# reTerm-HW-M-IOLINK-SUPPLY.net
KiCad netlist of a schematic drawn in Altium Designer
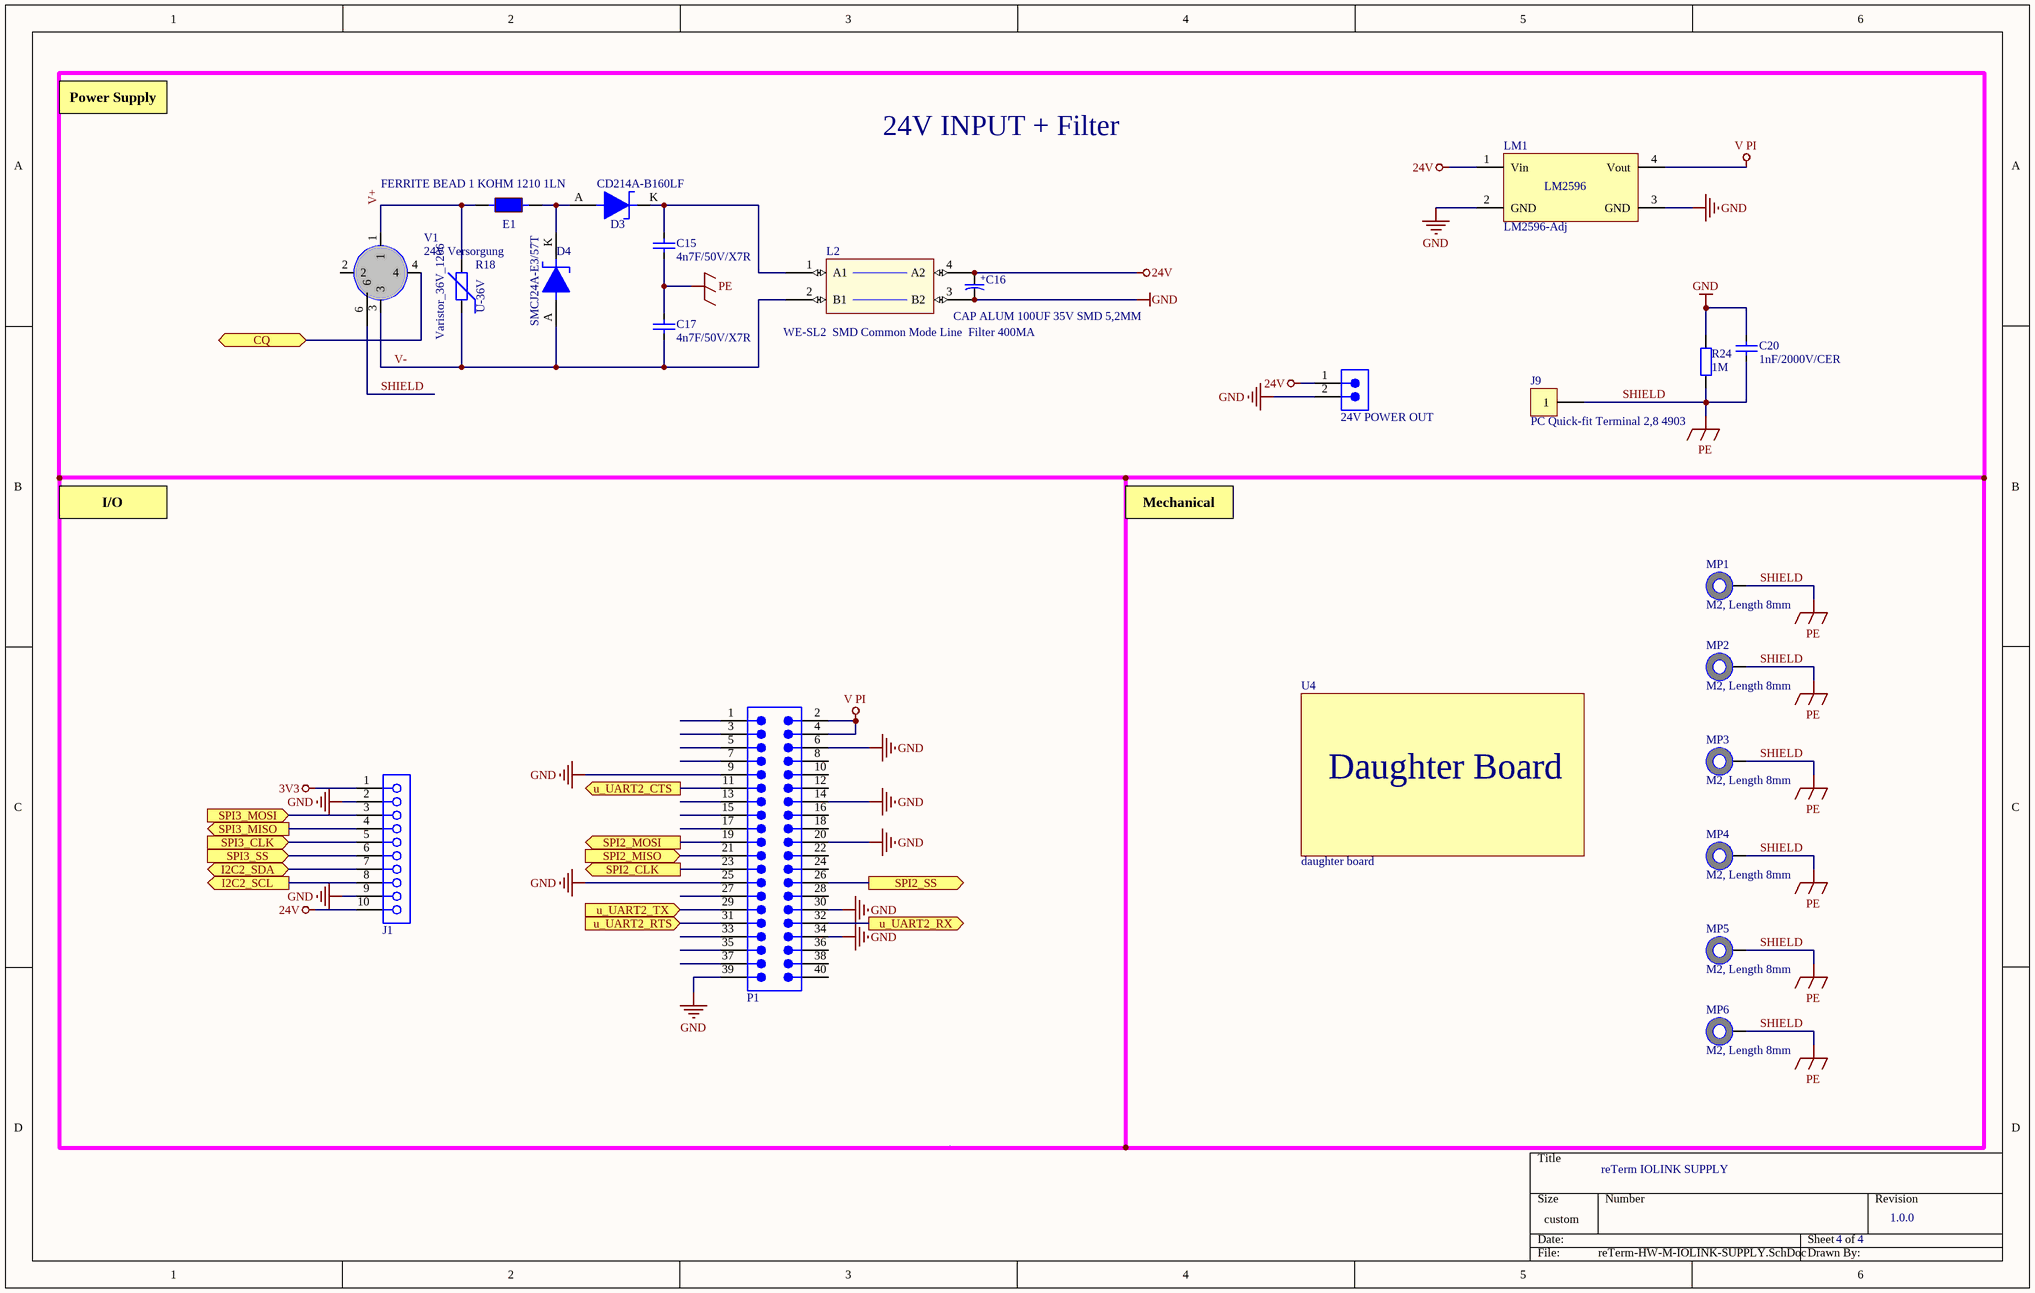
[diagram p0: reTerm-HW-M-IOLINK-SUPPLY.SchDoc]

(export (version "E")
  (design (tool "Eeschema 10.0.6"))
  (components
    (comp (ref "24V POWER OUT")
      (value "691322310002")
      (footprint "WR Terminal, 3.81mm, 2p")
      (description "WR-TBL Series 322 Horizontal PCB Header, THT, pitch 3.81mm, 2p")
      (fields (field (name "MANUFACTURER") "Wurth Elektronik"))
      (libsource (lib "HE_Lib") (part "WR Terminal, 3.81mm, 2p"))
    )
    (comp (ref "C15")
      (value "4n7F/50V/X7R")
      (footprint "C0603")
      (description "4n7F/50V/X7R 0603")
      (libsource (lib "HE_Lib") (part "CAP_4n7F_50V_X7R"))
    )
    (comp (ref "C16")
      (value "CAP ALUM 100UF 35V SMD 5,2MM")
      (footprint "SMD_ELKO_CASE_D8")
      (description "CAP ALUM 100UF 20% 35V SMD 5,2MM")
      (libsource (lib "HE_Lib") (part "CAP ALUM 100UF 20% 35V SMD 5,2MM"))
    )
    (comp (ref "C17")
      (value "4n7F/50V/X7R")
      (footprint "C0603")
      (description "4n7F/50V/X7R 0603")
      (libsource (lib "HE_Lib") (part "CAP_4n7F_50V_X7R"))
    )
    (comp (ref "C20")
      (value "1nF/2000V/CER")
      (footprint "C1206")
      (description "1nF/2000V/CER 1206")
      (libsource (lib "HE_Lib") (part "CAP_1nF_2000V_CER_1"))
    )
    (comp (ref "D3")
      (value "CD214A-B160LF")
      (footprint "DO-214AC")
      (description "DIODE SCHOTTKY 60V 1A SMA")
      (libsource (lib "HE_Lib") (part "CD214A-B160LF"))
    )
    (comp (ref "D4")
      (value "SMCJ24A-E3/57T")
      (footprint "DO-214AB")
      (description "TVS DIODE 24VWM 38.9VC SMC")
      (libsource (lib "HE_Lib") (part "SMCJ24A-E3/57T"))
    )
    (comp (ref "E1")
      (value "FERRITE BEAD 1 KOHM 1210 1LN")
      (footprint "L1210")
      (libsource (lib "HE_Lib") (part "FERRITE BEAD 1 KOHM 1210 1LN"))
    )
    (comp (ref "J1")
      (value "62001011821")
      (footprint "Header, 2.00 mm, THT, 10p")
      (description "WR-PHD Socket Header, THT, Vertical, pitch 2mm, 1 Row, 10P")
      (fields (field (name "MANUFACTURER") "Wurth Elektronik"))
      (libsource (lib "HE_Lib") (part "WR-PHD Header, THT, 2mm, 10P"))
    )
    (comp (ref "J9")
      (value "PC Quick-fit Terminal 2,8 4903")
      (footprint "PC-Quick-FIT-TERMINAL-4903")
      (description "PC Quick-Fit Terminal 2,8\r\nKeystone 4903")
      (libsource (lib "HE_Lib") (part "PC Quick-fit Terminal 2,8 4903"))
    )
    (comp (ref "L2")
      (value "WE-SL2  SMD Common Mode Line  Filter 400MA")
      (footprint "WE-SL2")
      (description "EMI Signal Line Filter WE-SL2 744229")
      (libsource (lib "HE_Lib") (part "WE-SL2 COMMON-CHOKE 400MA"))
    )
    (comp (ref "LM1")
      (value "LM2596-Adj")
      (footprint "lm2596")
      (description "Designed By @Alixahedi")
      (libsource (lib "HE_Lib") (part "LM2596-Adj"))
    )
    (comp (ref "MP1")
      (value "M2, Length 8mm")
      (footprint "9774080243")
      (description "WA-SMSI SMT Steel Spacer, M2 Thread Internal, Length 8mm")
      (fields (field (name "PARTNUMBER") "9774080243R") (field (name "PUBLISHER") "Wurth Elektronik"))
      (libsource (lib "WA-SMSI_M2 Thread Internal") (part "9774080243R"))
    )
    (comp (ref "MP2")
      (value "M2, Length 8mm")
      (footprint "9774080243")
      (description "WA-SMSI SMT Steel Spacer, M2 Thread Internal, Length 8mm")
      (fields (field (name "PARTNUMBER") "9774080243R") (field (name "PUBLISHER") "Wurth Elektronik"))
      (libsource (lib "WA-SMSI_M2 Thread Internal") (part "9774080243R"))
    )
    (comp (ref "MP3")
      (value "M2, Length 8mm")
      (footprint "9774080243")
      (description "WA-SMSI SMT Steel Spacer, M2 Thread Internal, Length 8mm")
      (fields (field (name "PARTNUMBER") "9774080243R") (field (name "PUBLISHER") "Wurth Elektronik"))
      (libsource (lib "WA-SMSI_M2 Thread Internal") (part "9774080243R"))
    )
    (comp (ref "MP4")
      (value "M2, Length 8mm")
      (footprint "9774080243")
      (description "WA-SMSI SMT Steel Spacer, M2 Thread Internal, Length 8mm")
      (fields (field (name "PARTNUMBER") "9774080243R") (field (name "PUBLISHER") "Wurth Elektronik"))
      (libsource (lib "WA-SMSI_M2 Thread Internal") (part "9774080243R"))
    )
    (comp (ref "MP5")
      (value "M2, Length 8mm")
      (footprint "9774080243")
      (description "WA-SMSI SMT Steel Spacer, M2 Thread Internal, Length 8mm")
      (fields (field (name "PARTNUMBER") "9774080243R") (field (name "PUBLISHER") "Wurth Elektronik"))
      (libsource (lib "WA-SMSI_M2 Thread Internal") (part "9774080243R"))
    )
    (comp (ref "MP6")
      (value "M2, Length 8mm")
      (footprint "9774080243")
      (description "WA-SMSI SMT Steel Spacer, M2 Thread Internal, Length 8mm")
      (fields (field (name "PARTNUMBER") "9774080243R") (field (name "PUBLISHER") "Wurth Elektronik"))
      (libsource (lib "WA-SMSI_M2 Thread Internal") (part "9774080243R"))
    )
    (comp (ref "P1")
      (value "61304021121")
      (footprint "WR-PHD Pin Header, THT, 2.54mm, 40P")
      (description "WR-PHD Pin Header, THT, Vertical, pitch 2.54mm, 2 Row, 40P")
      (fields (field (name "MANUFACTURER") "Wurth Elektronik"))
      (libsource (lib "HE_Lib") (part "WR-PHD Pin Header, 2.54mm, 40P"))
    )
    (comp (ref "R18")
      (value "Varistor_36V_1206")
      (footprint "V1206")
      (description "Varistor_36V_1206_82541300")
      (libsource (lib "HE_Lib") (part "Varistor_36V_1206"))
    )
    (comp (ref "R24")
      (value "1M")
      (footprint "R1206")
      (description "Resistor-1M")
      (libsource (lib "HE_Lib") (part "R1M"))
    )
    (comp (ref "U4")
      (value "daughter board")
      (footprint "daughter board")
      (libsource (lib "daughter board") (part "daughter board"))
    )
    (comp (ref "V1")
      (value "24V Versorgung")
      (footprint "M12/4POL/A-COD/STECKER")
      (description "M12 Flanschdose 4-polig Serie 713/763")
      (libsource (lib "HE_Lib") (part "M12 Flanschdose 4 Serie 713/763"))
    )
  )
  (nets
    (net (code "1") (name "/CQ") (class "Default")
      (node (ref "V1") (pin "4") (pinfunction "4_4") (pintype "passive"))
    )
    (net (code "2") (name "/I2C2_SCL") (class "Default")
      (node (ref "J1") (pin "8") (pinfunction "8_8") (pintype "passive"))
    )
    (net (code "3") (name "/I2C2_SDA") (class "Default")
      (node (ref "J1") (pin "7") (pinfunction "7_7") (pintype "passive"))
    )
    (net (code "4") (name "/SPI2_CLK") (class "Default")
      (node (ref "P1") (pin "23") (pinfunction "23_23") (pintype "passive"))
    )
    (net (code "5") (name "/SPI2_MISO") (class "Default")
      (node (ref "P1") (pin "21") (pinfunction "21_21") (pintype "passive"))
    )
    (net (code "6") (name "/SPI2_MOSI") (class "Default")
      (node (ref "P1") (pin "19") (pinfunction "19_19") (pintype "passive"))
    )
    (net (code "7") (name "/SPI2_SS") (class "Default")
      (node (ref "P1") (pin "26") (pinfunction "26_26") (pintype "passive"))
    )
    (net (code "8") (name "/SPI3_CLK") (class "Default")
      (node (ref "J1") (pin "5") (pinfunction "5_5") (pintype "passive"))
    )
    (net (code "9") (name "/SPI3_MISO") (class "Default")
      (node (ref "J1") (pin "4") (pinfunction "4_4") (pintype "passive"))
    )
    (net (code "10") (name "/SPI3_MOSI") (class "Default")
      (node (ref "J1") (pin "3") (pinfunction "3_3") (pintype "passive"))
    )
    (net (code "11") (name "/SPI3_SS") (class "Default")
      (node (ref "J1") (pin "6") (pinfunction "6_6") (pintype "passive"))
    )
    (net (code "12") (name "/V+") (class "Default")
      (node (ref "E1") (pin "1") (pinfunction "1_1") (pintype "passive"))
      (node (ref "R18") (pin "2") (pinfunction "2_2") (pintype "passive"))
      (node (ref "V1") (pin "1") (pinfunction "1_1") (pintype "passive"))
    )
    (net (code "13") (name "/V-") (class "Default")
      (node (ref "C17") (pin "2") (pinfunction "2_2") (pintype "passive"))
      (node (ref "D4") (pin "A") (pinfunction "A_A") (pintype "passive"))
      (node (ref "L2") (pin "2") (pinfunction "B1_2") (pintype "bidirectional"))
      (node (ref "R18") (pin "1") (pinfunction "1_1") (pintype "passive"))
      (node (ref "V1") (pin "3") (pinfunction "3_3") (pintype "passive"))
    )
    (net (code "14") (name "/u_UART2_CTS") (class "Default")
      (node (ref "P1") (pin "11") (pinfunction "11_11") (pintype "passive"))
    )
    (net (code "15") (name "/u_UART2_RTS") (class "Default")
      (node (ref "P1") (pin "31") (pinfunction "31_31") (pintype "passive"))
    )
    (net (code "16") (name "/u_UART2_RX") (class "Default")
      (node (ref "P1") (pin "32") (pinfunction "32_32") (pintype "passive"))
    )
    (net (code "17") (name "/u_UART2_TX") (class "Default")
      (node (ref "P1") (pin "29") (pinfunction "29_29") (pintype "passive"))
    )
    (net (code "18") (name "3V3") (class "Default")
      (node (ref "J1") (pin "1") (pinfunction "1_1") (pintype "passive"))
    )
    (net (code "19") (name "24V") (class "Default")
      (node (ref "24V POWER OUT") (pin "1") (pinfunction "1_1") (pintype "passive"))
      (node (ref "C16") (pin "1") (pinfunction "1_1") (pintype "passive"))
      (node (ref "J1") (pin "10") (pinfunction "10_10") (pintype "passive"))
      (node (ref "L2") (pin "4") (pinfunction "A2_4") (pintype "bidirectional"))
      (node (ref "LM1") (pin "1") (pinfunction "Vin_1") (pintype "passive"))
    )
    (net (code "20") (name "GND") (class "Default")
      (node (ref "24V POWER OUT") (pin "2") (pinfunction "2_2") (pintype "passive"))
      (node (ref "C16") (pin "2") (pinfunction "2_2") (pintype "passive"))
      (node (ref "C20") (pin "2") (pinfunction "2_2") (pintype "passive"))
      (node (ref "J1") (pin "2") (pinfunction "2_2") (pintype "passive"))
      (node (ref "J1") (pin "9") (pinfunction "9_9") (pintype "passive"))
      (node (ref "L2") (pin "3") (pinfunction "B2_3") (pintype "bidirectional"))
      (node (ref "LM1") (pin "2") (pinfunction "GND_2") (pintype "passive"))
      (node (ref "LM1") (pin "3") (pinfunction "GND_3") (pintype "passive"))
      (node (ref "P1") (pin "14") (pinfunction "14_14") (pintype "passive"))
      (node (ref "P1") (pin "20") (pinfunction "20_20") (pintype "passive"))
      (node (ref "P1") (pin "25") (pinfunction "25_25") (pintype "passive"))
      (node (ref "P1") (pin "30") (pinfunction "30_30") (pintype "passive"))
      (node (ref "P1") (pin "34") (pinfunction "34_34") (pintype "passive"))
      (node (ref "P1") (pin "39") (pinfunction "39_39") (pintype "passive"))
      (node (ref "P1") (pin "6") (pinfunction "6_6") (pintype "passive"))
      (node (ref "P1") (pin "9") (pinfunction "9_9") (pintype "passive"))
      (node (ref "R24") (pin "2") (pinfunction "2_2") (pintype "passive"))
    )
    (net (code "21") (name "Net-(D3-PadA)") (class "Default")
      (node (ref "D3") (pin "A") (pinfunction "A_A") (pintype "passive"))
      (node (ref "D4") (pin "K") (pinfunction "K_K") (pintype "passive"))
      (node (ref "E1") (pin "2") (pinfunction "1_2") (pintype "passive"))
    )
    (net (code "22") (name "Net-(L2-A1)") (class "Default")
      (node (ref "C15") (pin "2") (pinfunction "2_2") (pintype "passive"))
      (node (ref "D3") (pin "K") (pinfunction "K_K") (pintype "passive"))
      (node (ref "L2") (pin "1") (pinfunction "A1_1") (pintype "bidirectional"))
    )
    (net (code "23") (name "PE") (class "Default")
      (node (ref "C15") (pin "1") (pinfunction "1_1") (pintype "passive"))
      (node (ref "C17") (pin "1") (pinfunction "1_1") (pintype "passive"))
      (node (ref "C20") (pin "1") (pinfunction "1_1") (pintype "passive"))
      (node (ref "J9") (pin "1") (pinfunction "1_1") (pintype "passive"))
      (node (ref "MP1") (pin "1") (pinfunction "1_1") (pintype "passive"))
      (node (ref "MP2") (pin "1") (pinfunction "1_1") (pintype "passive"))
      (node (ref "MP3") (pin "1") (pinfunction "1_1") (pintype "passive"))
      (node (ref "MP4") (pin "1") (pinfunction "1_1") (pintype "passive"))
      (node (ref "MP5") (pin "1") (pinfunction "1_1") (pintype "passive"))
      (node (ref "MP6") (pin "1") (pinfunction "1_1") (pintype "passive"))
      (node (ref "R24") (pin "1") (pinfunction "1_1") (pintype "passive"))
      (node (ref "V1") (pin "6") (pinfunction "6_6") (pintype "passive"))
    )
    (net (code "24") (name "V PI") (class "Default")
      (node (ref "LM1") (pin "4") (pinfunction "Vout_4") (pintype "passive"))
      (node (ref "P1") (pin "2") (pinfunction "2_2") (pintype "passive"))
      (node (ref "P1") (pin "4") (pinfunction "4_4") (pintype "passive"))
    )
    (net (code "25") (name "unconnected-(P1-Pad1)") (class "Default")
      (node (ref "P1") (pin "1") (pinfunction "1_1") (pintype "passive"))
    )
    (net (code "26") (name "unconnected-(P1-Pad3)") (class "Default")
      (node (ref "P1") (pin "3") (pinfunction "3_3") (pintype "passive"))
    )
    (net (code "27") (name "unconnected-(P1-Pad5)") (class "Default")
      (node (ref "P1") (pin "5") (pinfunction "5_5") (pintype "passive"))
    )
    (net (code "28") (name "unconnected-(P1-Pad7)") (class "Default")
      (node (ref "P1") (pin "7") (pinfunction "7_7") (pintype "passive"))
    )
    (net (code "29") (name "unconnected-(P1-Pad8)") (class "Default")
      (node (ref "P1") (pin "8") (pinfunction "8_8") (pintype "passive"))
    )
    (net (code "30") (name "unconnected-(P1-Pad10)") (class "Default")
      (node (ref "P1") (pin "10") (pinfunction "10_10") (pintype "passive"))
    )
    (net (code "31") (name "unconnected-(P1-Pad12)") (class "Default")
      (node (ref "P1") (pin "12") (pinfunction "12_12") (pintype "passive"))
    )
    (net (code "32") (name "unconnected-(P1-Pad13)") (class "Default")
      (node (ref "P1") (pin "13") (pinfunction "13_13") (pintype "passive"))
    )
    (net (code "33") (name "unconnected-(P1-Pad15)") (class "Default")
      (node (ref "P1") (pin "15") (pinfunction "15_15") (pintype "passive"))
    )
    (net (code "34") (name "unconnected-(P1-Pad16)") (class "Default")
      (node (ref "P1") (pin "16") (pinfunction "16_16") (pintype "passive"))
    )
    (net (code "35") (name "unconnected-(P1-Pad17)") (class "Default")
      (node (ref "P1") (pin "17") (pinfunction "17_17") (pintype "passive"))
    )
    (net (code "36") (name "unconnected-(P1-Pad18)") (class "Default")
      (node (ref "P1") (pin "18") (pinfunction "18_18") (pintype "passive"))
    )
    (net (code "37") (name "unconnected-(P1-Pad22)") (class "Default")
      (node (ref "P1") (pin "22") (pinfunction "22_22") (pintype "passive"))
    )
    (net (code "38") (name "unconnected-(P1-Pad24)") (class "Default")
      (node (ref "P1") (pin "24") (pinfunction "24_24") (pintype "passive"))
    )
    (net (code "39") (name "unconnected-(P1-Pad27)") (class "Default")
      (node (ref "P1") (pin "27") (pinfunction "27_27") (pintype "passive"))
    )
    (net (code "40") (name "unconnected-(P1-Pad28)") (class "Default")
      (node (ref "P1") (pin "28") (pinfunction "28_28") (pintype "passive"))
    )
    (net (code "41") (name "unconnected-(P1-Pad33)") (class "Default")
      (node (ref "P1") (pin "33") (pinfunction "33_33") (pintype "passive"))
    )
    (net (code "42") (name "unconnected-(P1-Pad35)") (class "Default")
      (node (ref "P1") (pin "35") (pinfunction "35_35") (pintype "passive"))
    )
    (net (code "43") (name "unconnected-(P1-Pad36)") (class "Default")
      (node (ref "P1") (pin "36") (pinfunction "36_36") (pintype "passive"))
    )
    (net (code "44") (name "unconnected-(P1-Pad37)") (class "Default")
      (node (ref "P1") (pin "37") (pinfunction "37_37") (pintype "passive"))
    )
    (net (code "45") (name "unconnected-(P1-Pad38)") (class "Default")
      (node (ref "P1") (pin "38") (pinfunction "38_38") (pintype "passive"))
    )
    (net (code "46") (name "unconnected-(P1-Pad40)") (class "Default")
      (node (ref "P1") (pin "40") (pinfunction "40_40") (pintype "passive"))
    )
    (net (code "47") (name "unconnected-(V1-Pad2)") (class "Default")
      (node (ref "V1") (pin "2") (pinfunction "2_2") (pintype "passive"))
    )
  )
)
